# facebard-7-sensor-smd.net
KiCad netlist of a schematic drawn in EAGLE
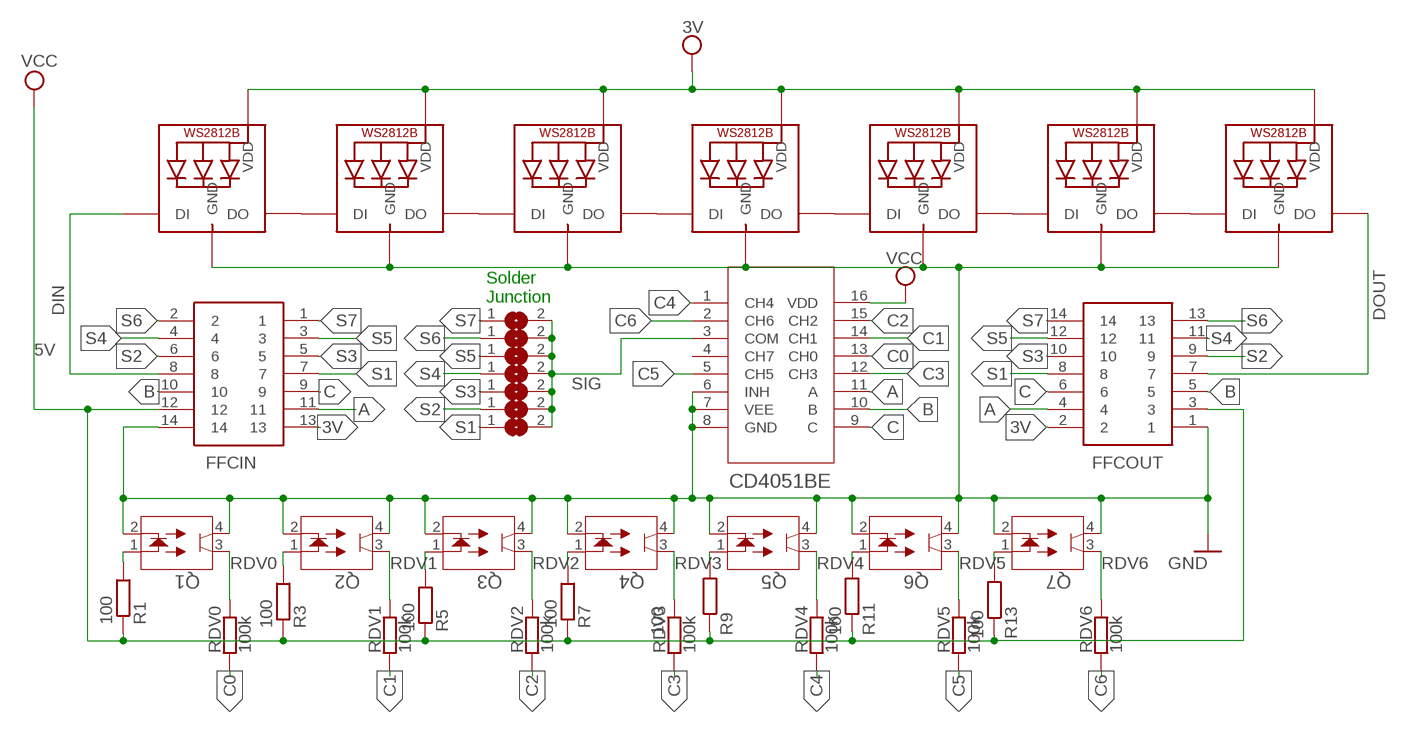
[diagram p0: schematic, sheet 1]

(export (version "E")
  (design (tool "Eeschema 10.0.6"))
  (components
    (comp (ref "FFCIN")
      (value "52806-1410")
      (footprint "eagle-import:528061410")
      (fields (field (name "MOUSER_PART_NUMBER") "538-52806-1410"))
      (libsource (lib "eagle-import") (part "52806-1410"))
    )
    (comp (ref "FFCOUT")
      (value "52806-1410")
      (footprint "eagle-import:528061410")
      (fields (field (name "MOUSER_PART_NUMBER") "538-52806-1410"))
      (libsource (lib "eagle-import") (part "52806-1410"))
    )
    (comp (ref "LED1")
      (value "WS2812B3535")
      (footprint "eagle-import:LED3535")
      (libsource (lib "eagle-import") (part "WS2812B3535"))
    )
    (comp (ref "LED2")
      (value "WS2812B3535")
      (footprint "eagle-import:LED3535")
      (libsource (lib "eagle-import") (part "WS2812B3535"))
    )
    (comp (ref "LED3")
      (value "WS2812B3535")
      (footprint "eagle-import:LED3535")
      (libsource (lib "eagle-import") (part "WS2812B3535"))
    )
    (comp (ref "LED4")
      (value "WS2812B3535")
      (footprint "eagle-import:LED3535")
      (libsource (lib "eagle-import") (part "WS2812B3535"))
    )
    (comp (ref "LED5")
      (value "WS2812B3535")
      (footprint "eagle-import:LED3535")
      (libsource (lib "eagle-import") (part "WS2812B3535"))
    )
    (comp (ref "LED6")
      (value "WS2812B3535")
      (footprint "eagle-import:LED3535")
      (libsource (lib "eagle-import") (part "WS2812B3535"))
    )
    (comp (ref "LED7")
      (value "WS2812B3535")
      (footprint "eagle-import:LED3535")
      (libsource (lib "eagle-import") (part "WS2812B3535"))
    )
    (comp (ref "Q1")
      (value "QRE1113")
      (footprint "eagle-import:DIP4_100AQ_ONS")
      (fields (field (name "COPYRIGHT") "Copyright (C) 2024 Ultra Librarian. All rights reserved."))
      (libsource (lib "eagle-import") (part "QRE1113"))
    )
    (comp (ref "Q2")
      (value "QRE1113")
      (footprint "eagle-import:DIP4_100AQ_ONS")
      (fields (field (name "COPYRIGHT") "Copyright (C) 2024 Ultra Librarian. All rights reserved."))
      (libsource (lib "eagle-import") (part "QRE1113"))
    )
    (comp (ref "Q3")
      (value "QRE1113")
      (footprint "eagle-import:DIP4_100AQ_ONS")
      (fields (field (name "COPYRIGHT") "Copyright (C) 2024 Ultra Librarian. All rights reserved."))
      (libsource (lib "eagle-import") (part "QRE1113"))
    )
    (comp (ref "Q4")
      (value "QRE1113")
      (footprint "eagle-import:DIP4_100AQ_ONS")
      (fields (field (name "COPYRIGHT") "Copyright (C) 2024 Ultra Librarian. All rights reserved."))
      (libsource (lib "eagle-import") (part "QRE1113"))
    )
    (comp (ref "Q5")
      (value "QRE1113")
      (footprint "eagle-import:DIP4_100AQ_ONS")
      (fields (field (name "COPYRIGHT") "Copyright (C) 2024 Ultra Librarian. All rights reserved."))
      (libsource (lib "eagle-import") (part "QRE1113"))
    )
    (comp (ref "Q6")
      (value "QRE1113")
      (footprint "eagle-import:DIP4_100AQ_ONS")
      (fields (field (name "COPYRIGHT") "Copyright (C) 2024 Ultra Librarian. All rights reserved."))
      (libsource (lib "eagle-import") (part "QRE1113"))
    )
    (comp (ref "Q7")
      (value "QRE1113")
      (footprint "eagle-import:DIP4_100AQ_ONS")
      (fields (field (name "COPYRIGHT") "Copyright (C) 2024 Ultra Librarian. All rights reserved."))
      (libsource (lib "eagle-import") (part "QRE1113"))
    )
    (comp (ref "R1")
      (value "100")
      (footprint "eagle-import:0207_10")
      (libsource (lib "eagle-import") (part "R-EU_0207/10"))
    )
    (comp (ref "R3")
      (value "100")
      (footprint "eagle-import:0207_10")
      (libsource (lib "eagle-import") (part "R-EU_0207/10"))
    )
    (comp (ref "R5")
      (value "100")
      (footprint "eagle-import:0207_10")
      (libsource (lib "eagle-import") (part "R-EU_0207/10"))
    )
    (comp (ref "R7")
      (value "100")
      (footprint "eagle-import:0207_10")
      (libsource (lib "eagle-import") (part "R-EU_0207/10"))
    )
    (comp (ref "R9")
      (value "100")
      (footprint "eagle-import:0207_10")
      (libsource (lib "eagle-import") (part "R-EU_0207/10"))
    )
    (comp (ref "R11")
      (value "100")
      (footprint "eagle-import:0207_10")
      (libsource (lib "eagle-import") (part "R-EU_0207/10"))
    )
    (comp (ref "R13")
      (value "100")
      (footprint "eagle-import:0207_10")
      (libsource (lib "eagle-import") (part "R-EU_0207/10"))
    )
    (comp (ref "RDV0")
      (value "100k")
      (footprint "eagle-import:0207_10")
      (libsource (lib "eagle-import") (part "R-EU_0207/10"))
    )
    (comp (ref "RDV1")
      (value "100k")
      (footprint "eagle-import:0207_10")
      (libsource (lib "eagle-import") (part "R-EU_0207/10"))
    )
    (comp (ref "RDV2")
      (value "100k")
      (footprint "eagle-import:0207_10")
      (libsource (lib "eagle-import") (part "R-EU_0207/10"))
    )
    (comp (ref "RDV3")
      (value "100k")
      (footprint "eagle-import:0207_10")
      (libsource (lib "eagle-import") (part "R-EU_0207/10"))
    )
    (comp (ref "RDV4")
      (value "100k")
      (footprint "eagle-import:0207_10")
      (libsource (lib "eagle-import") (part "R-EU_0207/10"))
    )
    (comp (ref "RDV5")
      (value "100k")
      (footprint "eagle-import:0207_10")
      (libsource (lib "eagle-import") (part "R-EU_0207/10"))
    )
    (comp (ref "RDV6")
      (value "100k")
      (footprint "eagle-import:0207_10")
      (libsource (lib "eagle-import") (part "R-EU_0207/10"))
    )
    (comp (ref "SJ1") (value "SJ") (footprint "eagle-import:SJ") (libsource (lib "eagle-import") (part "SJ")))
    (comp (ref "SJ2") (value "SJ") (footprint "eagle-import:SJ") (libsource (lib "eagle-import") (part "SJ")))
    (comp (ref "SJ3") (value "SJ") (footprint "eagle-import:SJ") (libsource (lib "eagle-import") (part "SJ")))
    (comp (ref "SJ4") (value "SJ") (footprint "eagle-import:SJ") (libsource (lib "eagle-import") (part "SJ")))
    (comp (ref "SJ5") (value "SJ") (footprint "eagle-import:SJ") (libsource (lib "eagle-import") (part "SJ")))
    (comp (ref "SJ6") (value "SJ") (footprint "eagle-import:SJ") (libsource (lib "eagle-import") (part "SJ")))
    (comp (ref "SJ7") (value "SJ") (footprint "eagle-import:SJ") (libsource (lib "eagle-import") (part "SJ")))
    (comp (ref "U1")
      (value "CD4051BE")
      (footprint "eagle-import:N16")
      (fields (field (name "COPYRIGHT") "Copyright (C) 2024 Ultra Librarian. All rights reserved."))
      (libsource (lib "eagle-import") (part "CD4051BE"))
    )
  )
  (nets
    (net (code "1") (name "/DIN") (class "Default")
      (node (ref "FFCIN") (pin "8") (pinfunction "8_8") (pintype "bidirectional"))
      (node (ref "LED1") (pin "1") (pinfunction "DI_1") (pintype "input"))
    )
    (net (code "2") (name "/DOUT") (class "Default")
      (node (ref "FFCOUT") (pin "7") (pinfunction "7_7") (pintype "bidirectional"))
      (node (ref "LED7") (pin "3") (pinfunction "DO_3") (pintype "output"))
    )
    (net (code "3") (name "/RDV0") (class "Default")
      (node (ref "Q1") (pin "3") (pinfunction "3_3") (pintype "passive"))
      (node (ref "RDV0") (pin "2") (pinfunction "2_2") (pintype "passive"))
    )
    (net (code "4") (name "/RDV1") (class "Default")
      (node (ref "Q2") (pin "3") (pinfunction "3_3") (pintype "passive"))
      (node (ref "RDV1") (pin "2") (pinfunction "2_2") (pintype "passive"))
    )
    (net (code "5") (name "/RDV2") (class "Default")
      (node (ref "Q3") (pin "3") (pinfunction "3_3") (pintype "passive"))
      (node (ref "RDV2") (pin "2") (pinfunction "2_2") (pintype "passive"))
    )
    (net (code "6") (name "/RDV3") (class "Default")
      (node (ref "Q4") (pin "3") (pinfunction "3_3") (pintype "passive"))
      (node (ref "RDV3") (pin "2") (pinfunction "2_2") (pintype "passive"))
    )
    (net (code "7") (name "/RDV4") (class "Default")
      (node (ref "Q5") (pin "3") (pinfunction "3_3") (pintype "passive"))
      (node (ref "RDV4") (pin "2") (pinfunction "2_2") (pintype "passive"))
    )
    (net (code "8") (name "/RDV5") (class "Default")
      (node (ref "Q6") (pin "3") (pinfunction "3_3") (pintype "passive"))
      (node (ref "RDV5") (pin "2") (pinfunction "2_2") (pintype "passive"))
    )
    (net (code "9") (name "/RDV6") (class "Default")
      (node (ref "Q7") (pin "3") (pinfunction "3_3") (pintype "passive"))
      (node (ref "RDV6") (pin "2") (pinfunction "2_2") (pintype "passive"))
    )
    (net (code "10") (name "/SIG") (class "Default")
      (node (ref "SJ1") (pin "2") (pinfunction "2_2") (pintype "passive"))
      (node (ref "SJ2") (pin "2") (pinfunction "2_2") (pintype "passive"))
      (node (ref "SJ3") (pin "2") (pinfunction "2_2") (pintype "passive"))
      (node (ref "SJ4") (pin "2") (pinfunction "2_2") (pintype "passive"))
      (node (ref "SJ5") (pin "2") (pinfunction "2_2") (pintype "passive"))
      (node (ref "SJ6") (pin "2") (pinfunction "2_2") (pintype "passive"))
      (node (ref "SJ7") (pin "2") (pinfunction "2_2") (pintype "passive"))
      (node (ref "U1") (pin "3") (pinfunction "COM_3") (pintype "bidirectional"))
    )
    (net (code "11") (name "3V") (class "Default")
      (node (ref "FFCIN") (pin "13") (pinfunction "13_13") (pintype "bidirectional"))
      (node (ref "FFCOUT") (pin "2") (pinfunction "2_2") (pintype "bidirectional"))
      (node (ref "LED1") (pin "2") (pinfunction "VDD_2") (pintype "power_in"))
      (node (ref "LED2") (pin "2") (pinfunction "VDD_2") (pintype "power_in"))
      (node (ref "LED3") (pin "2") (pinfunction "VDD_2") (pintype "power_in"))
      (node (ref "LED4") (pin "2") (pinfunction "VDD_2") (pintype "power_in"))
      (node (ref "LED5") (pin "2") (pinfunction "VDD_2") (pintype "power_in"))
      (node (ref "LED6") (pin "2") (pinfunction "VDD_2") (pintype "power_in"))
      (node (ref "LED7") (pin "2") (pinfunction "VDD_2") (pintype "power_in"))
    )
    (net (code "12") (name "A") (class "Default")
      (node (ref "FFCIN") (pin "11") (pinfunction "11_11") (pintype "bidirectional"))
      (node (ref "FFCOUT") (pin "4") (pinfunction "4_4") (pintype "bidirectional"))
      (node (ref "U1") (pin "11") (pinfunction "A_11") (pintype "passive"))
    )
    (net (code "13") (name "B") (class "Default")
      (node (ref "FFCIN") (pin "10") (pinfunction "10_10") (pintype "bidirectional"))
      (node (ref "FFCOUT") (pin "5") (pinfunction "5_5") (pintype "bidirectional"))
      (node (ref "U1") (pin "10") (pinfunction "B_10") (pintype "passive"))
    )
    (net (code "14") (name "C") (class "Default")
      (node (ref "FFCIN") (pin "9") (pinfunction "9_9") (pintype "bidirectional"))
      (node (ref "FFCOUT") (pin "6") (pinfunction "6_6") (pintype "bidirectional"))
      (node (ref "U1") (pin "9") (pinfunction "C_9") (pintype "passive"))
    )
    (net (code "15") (name "C0") (class "Default")
      (node (ref "RDV0") (pin "1") (pinfunction "1_1") (pintype "passive"))
      (node (ref "U1") (pin "13") (pinfunction "CH0_13") (pintype "bidirectional"))
    )
    (net (code "16") (name "C1") (class "Default")
      (node (ref "RDV1") (pin "1") (pinfunction "1_1") (pintype "passive"))
      (node (ref "U1") (pin "14") (pinfunction "CH1_14") (pintype "bidirectional"))
    )
    (net (code "17") (name "C2") (class "Default")
      (node (ref "RDV2") (pin "1") (pinfunction "1_1") (pintype "passive"))
      (node (ref "U1") (pin "15") (pinfunction "CH2_15") (pintype "bidirectional"))
    )
    (net (code "18") (name "C3") (class "Default")
      (node (ref "RDV3") (pin "1") (pinfunction "1_1") (pintype "passive"))
      (node (ref "U1") (pin "12") (pinfunction "CH3_12") (pintype "bidirectional"))
    )
    (net (code "19") (name "C4") (class "Default")
      (node (ref "RDV4") (pin "1") (pinfunction "1_1") (pintype "passive"))
      (node (ref "U1") (pin "1") (pinfunction "CH4_1") (pintype "bidirectional"))
    )
    (net (code "20") (name "C5") (class "Default")
      (node (ref "RDV5") (pin "1") (pinfunction "1_1") (pintype "passive"))
      (node (ref "U1") (pin "5") (pinfunction "CH5_5") (pintype "bidirectional"))
    )
    (net (code "21") (name "C6") (class "Default")
      (node (ref "RDV6") (pin "1") (pinfunction "1_1") (pintype "passive"))
      (node (ref "U1") (pin "2") (pinfunction "CH6_2") (pintype "bidirectional"))
    )
    (net (code "22") (name "GND") (class "Default")
      (node (ref "FFCIN") (pin "14") (pinfunction "14_14") (pintype "bidirectional"))
      (node (ref "FFCOUT") (pin "1") (pinfunction "1_1") (pintype "bidirectional"))
      (node (ref "LED1") (pin "4") (pinfunction "GND_4") (pintype "power_in"))
      (node (ref "LED2") (pin "4") (pinfunction "GND_4") (pintype "power_in"))
      (node (ref "LED3") (pin "4") (pinfunction "GND_4") (pintype "power_in"))
      (node (ref "LED4") (pin "4") (pinfunction "GND_4") (pintype "power_in"))
      (node (ref "LED5") (pin "4") (pinfunction "GND_4") (pintype "power_in"))
      (node (ref "LED6") (pin "4") (pinfunction "GND_4") (pintype "power_in"))
      (node (ref "LED7") (pin "4") (pinfunction "GND_4") (pintype "power_in"))
      (node (ref "Q1") (pin "2") (pinfunction "2_2") (pintype "passive"))
      (node (ref "Q1") (pin "4") (pinfunction "4_4") (pintype "passive"))
      (node (ref "Q2") (pin "2") (pinfunction "2_2") (pintype "passive"))
      (node (ref "Q2") (pin "4") (pinfunction "4_4") (pintype "passive"))
      (node (ref "Q3") (pin "2") (pinfunction "2_2") (pintype "passive"))
      (node (ref "Q3") (pin "4") (pinfunction "4_4") (pintype "passive"))
      (node (ref "Q4") (pin "2") (pinfunction "2_2") (pintype "passive"))
      (node (ref "Q4") (pin "4") (pinfunction "4_4") (pintype "passive"))
      (node (ref "Q5") (pin "2") (pinfunction "2_2") (pintype "passive"))
      (node (ref "Q5") (pin "4") (pinfunction "4_4") (pintype "passive"))
      (node (ref "Q6") (pin "2") (pinfunction "2_2") (pintype "passive"))
      (node (ref "Q6") (pin "4") (pinfunction "4_4") (pintype "passive"))
      (node (ref "Q7") (pin "2") (pinfunction "2_2") (pintype "passive"))
      (node (ref "Q7") (pin "4") (pinfunction "4_4") (pintype "passive"))
      (node (ref "U1") (pin "6") (pinfunction "INH_6") (pintype "passive"))
      (node (ref "U1") (pin "7") (pinfunction "VEE_7") (pintype "power_in"))
      (node (ref "U1") (pin "8") (pinfunction "GND_8") (pintype "power_in"))
    )
    (net (code "23") (name "Net-(LED1-DO)") (class "Default")
      (node (ref "LED1") (pin "3") (pinfunction "DO_3") (pintype "output"))
      (node (ref "LED2") (pin "1") (pinfunction "DI_1") (pintype "input"))
    )
    (net (code "24") (name "Net-(LED2-DO)") (class "Default")
      (node (ref "LED2") (pin "3") (pinfunction "DO_3") (pintype "output"))
      (node (ref "LED3") (pin "1") (pinfunction "DI_1") (pintype "input"))
    )
    (net (code "25") (name "Net-(LED3-DO)") (class "Default")
      (node (ref "LED3") (pin "3") (pinfunction "DO_3") (pintype "output"))
      (node (ref "LED4") (pin "1") (pinfunction "DI_1") (pintype "input"))
    )
    (net (code "26") (name "Net-(LED4-DO)") (class "Default")
      (node (ref "LED4") (pin "3") (pinfunction "DO_3") (pintype "output"))
      (node (ref "LED5") (pin "1") (pinfunction "DI_1") (pintype "input"))
    )
    (net (code "27") (name "Net-(LED5-DO)") (class "Default")
      (node (ref "LED5") (pin "3") (pinfunction "DO_3") (pintype "output"))
      (node (ref "LED6") (pin "1") (pinfunction "DI_1") (pintype "input"))
    )
    (net (code "28") (name "Net-(LED6-DO)") (class "Default")
      (node (ref "LED6") (pin "3") (pinfunction "DO_3") (pintype "output"))
      (node (ref "LED7") (pin "1") (pinfunction "DI_1") (pintype "input"))
    )
    (net (code "29") (name "Net-(Q1-Pad1)") (class "Default")
      (node (ref "Q1") (pin "1") (pinfunction "1_1") (pintype "passive"))
      (node (ref "R1") (pin "2") (pinfunction "2_2") (pintype "passive"))
    )
    (net (code "30") (name "Net-(Q2-Pad1)") (class "Default")
      (node (ref "Q2") (pin "1") (pinfunction "1_1") (pintype "passive"))
      (node (ref "R3") (pin "2") (pinfunction "2_2") (pintype "passive"))
    )
    (net (code "31") (name "Net-(Q3-Pad1)") (class "Default")
      (node (ref "Q3") (pin "1") (pinfunction "1_1") (pintype "passive"))
      (node (ref "R5") (pin "2") (pinfunction "2_2") (pintype "passive"))
    )
    (net (code "32") (name "Net-(Q4-Pad1)") (class "Default")
      (node (ref "Q4") (pin "1") (pinfunction "1_1") (pintype "passive"))
      (node (ref "R7") (pin "2") (pinfunction "2_2") (pintype "passive"))
    )
    (net (code "33") (name "Net-(Q5-Pad1)") (class "Default")
      (node (ref "Q5") (pin "1") (pinfunction "1_1") (pintype "passive"))
      (node (ref "R9") (pin "2") (pinfunction "2_2") (pintype "passive"))
    )
    (net (code "34") (name "Net-(Q6-Pad1)") (class "Default")
      (node (ref "Q6") (pin "1") (pinfunction "1_1") (pintype "passive"))
      (node (ref "R11") (pin "2") (pinfunction "2_2") (pintype "passive"))
    )
    (net (code "35") (name "Net-(Q7-Pad1)") (class "Default")
      (node (ref "Q7") (pin "1") (pinfunction "1_1") (pintype "passive"))
      (node (ref "R13") (pin "2") (pinfunction "2_2") (pintype "passive"))
    )
    (net (code "36") (name "S1") (class "Default")
      (node (ref "FFCIN") (pin "7") (pinfunction "7_7") (pintype "bidirectional"))
      (node (ref "FFCOUT") (pin "8") (pinfunction "8_8") (pintype "bidirectional"))
      (node (ref "SJ1") (pin "1") (pinfunction "1_1") (pintype "passive"))
    )
    (net (code "37") (name "S2") (class "Default")
      (node (ref "FFCIN") (pin "6") (pinfunction "6_6") (pintype "bidirectional"))
      (node (ref "FFCOUT") (pin "9") (pinfunction "9_9") (pintype "bidirectional"))
      (node (ref "SJ2") (pin "1") (pinfunction "1_1") (pintype "passive"))
    )
    (net (code "38") (name "S3") (class "Default")
      (node (ref "FFCIN") (pin "5") (pinfunction "5_5") (pintype "bidirectional"))
      (node (ref "FFCOUT") (pin "10") (pinfunction "10_10") (pintype "bidirectional"))
      (node (ref "SJ3") (pin "1") (pinfunction "1_1") (pintype "passive"))
    )
    (net (code "39") (name "S4") (class "Default")
      (node (ref "FFCIN") (pin "4") (pinfunction "4_4") (pintype "bidirectional"))
      (node (ref "FFCOUT") (pin "11") (pinfunction "11_11") (pintype "bidirectional"))
      (node (ref "SJ4") (pin "1") (pinfunction "1_1") (pintype "passive"))
    )
    (net (code "40") (name "S5") (class "Default")
      (node (ref "FFCIN") (pin "3") (pinfunction "3_3") (pintype "bidirectional"))
      (node (ref "FFCOUT") (pin "12") (pinfunction "12_12") (pintype "bidirectional"))
      (node (ref "SJ5") (pin "1") (pinfunction "1_1") (pintype "passive"))
    )
    (net (code "41") (name "S6") (class "Default")
      (node (ref "FFCIN") (pin "2") (pinfunction "2_2") (pintype "bidirectional"))
      (node (ref "FFCOUT") (pin "13") (pinfunction "13_13") (pintype "bidirectional"))
      (node (ref "SJ6") (pin "1") (pinfunction "1_1") (pintype "passive"))
    )
    (net (code "42") (name "S7") (class "Default")
      (node (ref "FFCIN") (pin "1") (pinfunction "1_1") (pintype "bidirectional"))
      (node (ref "FFCOUT") (pin "14") (pinfunction "14_14") (pintype "bidirectional"))
      (node (ref "SJ7") (pin "1") (pinfunction "1_1") (pintype "passive"))
    )
    (net (code "43") (name "VCC") (class "Default")
      (node (ref "FFCIN") (pin "12") (pinfunction "12_12") (pintype "bidirectional"))
      (node (ref "FFCOUT") (pin "3") (pinfunction "3_3") (pintype "bidirectional"))
      (node (ref "R1") (pin "1") (pinfunction "1_1") (pintype "passive"))
      (node (ref "R11") (pin "1") (pinfunction "1_1") (pintype "passive"))
      (node (ref "R13") (pin "1") (pinfunction "1_1") (pintype "passive"))
      (node (ref "R3") (pin "1") (pinfunction "1_1") (pintype "passive"))
      (node (ref "R5") (pin "1") (pinfunction "1_1") (pintype "passive"))
      (node (ref "R7") (pin "1") (pinfunction "1_1") (pintype "passive"))
      (node (ref "R9") (pin "1") (pinfunction "1_1") (pintype "passive"))
      (node (ref "U1") (pin "16") (pinfunction "VDD_16") (pintype "power_in"))
    )
    (net (code "44") (name "unconnected-(U1-CH7-Pad4)") (class "Default")
      (node (ref "U1") (pin "4") (pinfunction "CH7_4") (pintype "bidirectional"))
    )
  )
)
